# ReproAmp_V87_Stage_v0_01.net
KiCad netlist of a schematic drawn in Altium Designer
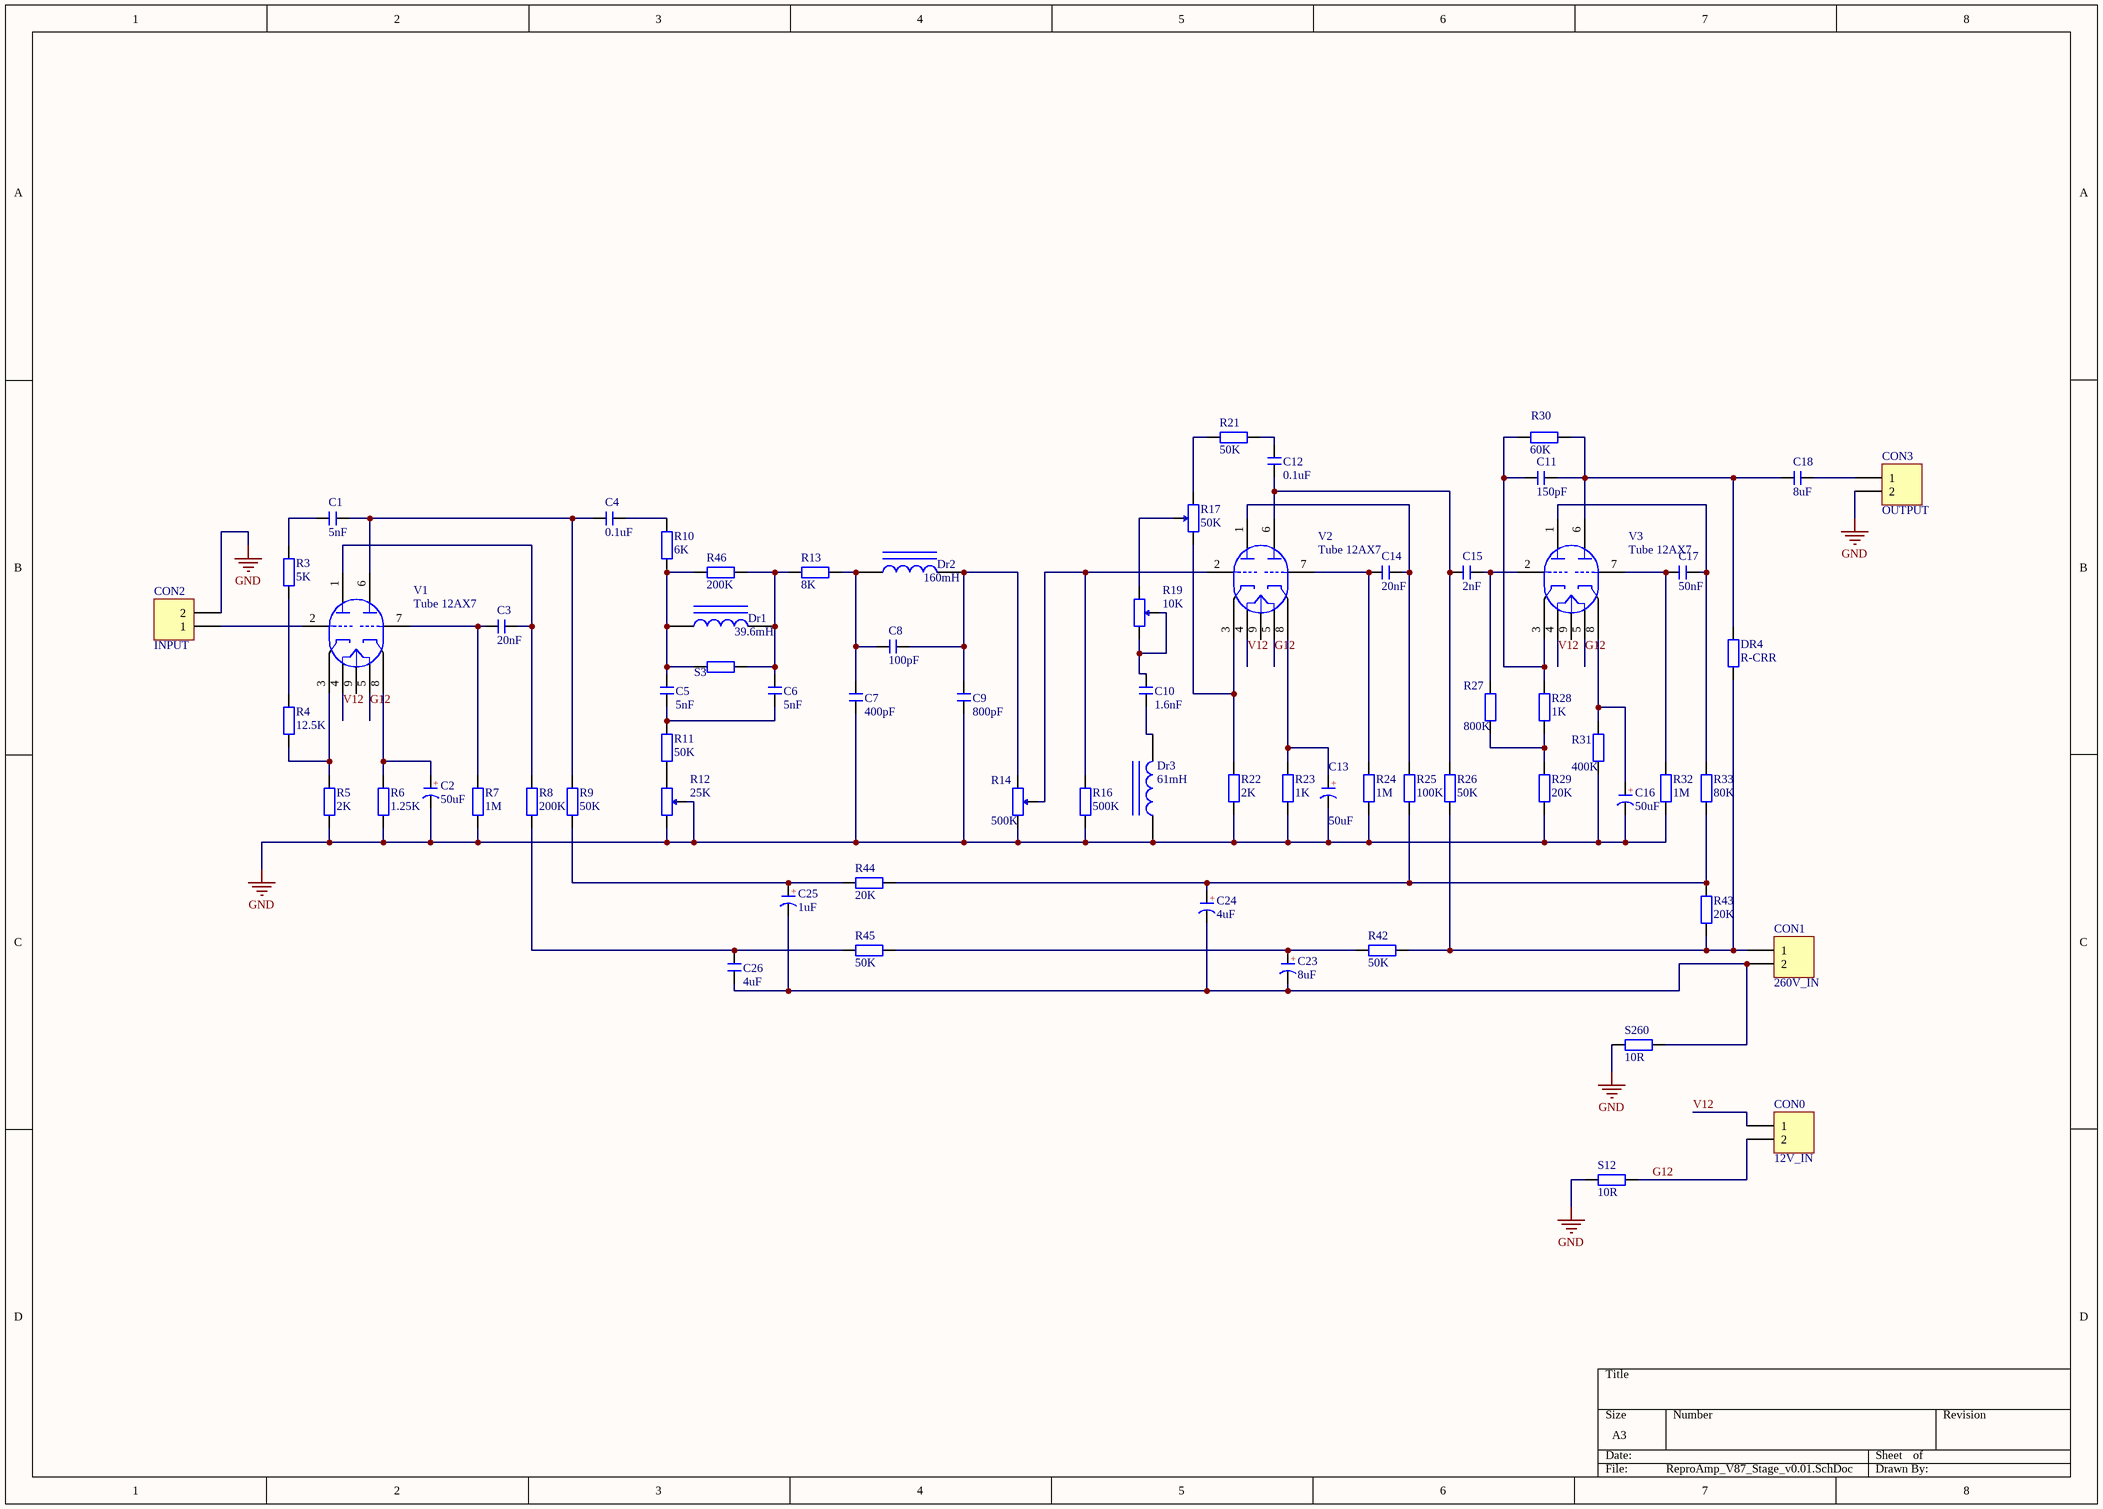
[diagram p0: ReproAmp_V87_Stage_v0.01.SchDoc]

(export (version "E")
  (design (tool "Eeschema 10.0.6"))
  (components
    (comp (ref "C1")
      (value "5nF")
      (footprint "CY 7.5*10*4")
      (description "CBB电容")
      (fields (field (name "版权归属") "源创客"))
      (libsource (lib "电阻-电容-电感") (part "C-CBB"))
    )
    (comp (ref "C2")
      (value "50uF")
      (footprint "CAP 5.0*12.5*20")
      (description "直插电解电容")
      (fields (field (name "版权归属") "源创客"))
      (libsource (lib "电阻-电容-电感") (part "C-CAP"))
    )
    (comp (ref "C3")
      (value "20nF")
      (footprint "CBB 10*12*8")
      (description "CBB电容")
      (fields (field (name "版权归属") "源创客"))
      (libsource (lib "电阻-电容-电感") (part "C-CBB"))
    )
    (comp (ref "C4")
      (value "0.1uF")
      (footprint "CBB 15*18*11")
      (description "CBB电容")
      (fields (field (name "版权归属") "源创客"))
      (libsource (lib "电阻-电容-电感") (part "C-CBB"))
    )
    (comp (ref "C5")
      (value "5nF")
      (footprint "CBB 7.2*7.2*13")
      (description "CBB电容")
      (fields (field (name "版权归属") "源创客"))
      (libsource (lib "电阻-电容-电感") (part "C-CBB"))
    )
    (comp (ref "C6")
      (value "5nF")
      (footprint "CBB 7.2*7.2*13")
      (description "CBB电容")
      (fields (field (name "版权归属") "源创客"))
      (libsource (lib "电阻-电容-电感") (part "C-CBB"))
    )
    (comp (ref "C7")
      (value "400pF")
      (footprint "CBB 7.2*7.2*13")
      (description "CBB电容")
      (fields (field (name "版权归属") "源创客"))
      (libsource (lib "电阻-电容-电感") (part "C-CBB"))
    )
    (comp (ref "C8")
      (value "100pF")
      (footprint "CBB 7.2*7.2*13")
      (description "CBB电容")
      (fields (field (name "版权归属") "源创客"))
      (libsource (lib "电阻-电容-电感") (part "C-CBB"))
    )
    (comp (ref "C9")
      (value "800pF")
      (footprint "CBB 7.2*7.2*13")
      (description "CBB电容")
      (fields (field (name "版权归属") "源创客"))
      (libsource (lib "电阻-电容-电感") (part "C-CBB"))
    )
    (comp (ref "C10")
      (value "1.6nF")
      (footprint "CBB 7.2*7.2*13")
      (description "CBB电容")
      (fields (field (name "版权归属") "源创客"))
      (libsource (lib "电阻-电容-电感") (part "C-CBB"))
    )
    (comp (ref "C11")
      (value "150pF")
      (footprint "CBB 15*18*11")
      (description "CBB电容")
      (fields (field (name "版权归属") "源创客"))
      (libsource (lib "电阻-电容-电感") (part "C-CBB"))
    )
    (comp (ref "C12")
      (value "0.1uF")
      (footprint "CBB 15*18*11")
      (description "CBB电容")
      (fields (field (name "版权归属") "源创客"))
      (libsource (lib "电阻-电容-电感") (part "C-CBB"))
    )
    (comp (ref "C13")
      (value "50uF")
      (footprint "CAP 5.0*12.5*20")
      (description "直插电解电容")
      (fields (field (name "版权归属") "源创客"))
      (libsource (lib "电阻-电容-电感") (part "C-CAP"))
    )
    (comp (ref "C14")
      (value "20nF")
      (footprint "CBB 10*12*8")
      (description "CBB电容")
      (fields (field (name "版权归属") "源创客"))
      (libsource (lib "电阻-电容-电感") (part "C-CBB"))
    )
    (comp (ref "C15")
      (value "2nF")
      (footprint "CY 7.5*8*4")
      (description "CBB电容")
      (fields (field (name "版权归属") "源创客"))
      (libsource (lib "电阻-电容-电感") (part "C-CBB"))
    )
    (comp (ref "C16")
      (value "50uF")
      (footprint "CAP 5.0*12.5*20")
      (description "直插电解电容")
      (fields (field (name "版权归属") "源创客"))
      (libsource (lib "电阻-电容-电感") (part "C-CAP"))
    )
    (comp (ref "C17")
      (value "50nF")
      (footprint "CBB 15*18*11")
      (description "CBB电容")
      (fields (field (name "版权归属") "源创客"))
      (libsource (lib "电阻-电容-电感") (part "C-CBB"))
    )
    (comp (ref "C18")
      (value "8uF")
      (footprint "CBB 50*30*30")
      (description "CBB电容")
      (fields (field (name "版权归属") "源创客"))
      (libsource (lib "电阻-电容-电感") (part "C-CBB"))
    )
    (comp (ref "C23")
      (value "8uF")
      (footprint "CAP 5.0*12.5*20")
      (description "直插电解电容")
      (fields (field (name "版权归属") "源创客"))
      (libsource (lib "电阻-电容-电感") (part "C-CAP"))
    )
    (comp (ref "C24")
      (value "4uF")
      (footprint "CAP 5.0*12.5*20")
      (description "直插电解电容")
      (fields (field (name "版权归属") "源创客"))
      (libsource (lib "电阻-电容-电感") (part "C-CAP"))
    )
    (comp (ref "C25")
      (value "1uF")
      (footprint "CAP 5.0*12.5*20")
      (description "直插电解电容")
      (fields (field (name "版权归属") "源创客"))
      (libsource (lib "电阻-电容-电感") (part "C-CAP"))
    )
    (comp (ref "C26")
      (value "4uF")
      (footprint "CBB 20*23*17")
      (description "CBB电容")
      (fields (field (name "版权归属") "源创客"))
      (libsource (lib "电阻-电容-电感") (part "C-CBB"))
    )
    (comp (ref "CON0") (value "12V_IN") (footprint "HX5.08-2L") (libsource (lib "") (part "EDG5.08-2P_1")))
    (comp (ref "CON1") (value "260V_IN") (footprint "HX5.08-2L") (libsource (lib "") (part "EDG5.08-2P_1")))
    (comp (ref "CON2")
      (value "INPUT")
      (footprint "HX5.08-2L")
      (libsource (lib "Connectors") (part "EDG5.08-2P"))
    )
    (comp (ref "CON3") (value "OUTPUT") (footprint "HX5.08-2L") (libsource (lib "") (part "EDG5.08-2P_1")))
    (comp (ref "Dr1")
      (value "39.6mH")
      (footprint "AXIAL-0.5")
      (description "Magnetic-Core Inductor")
      (fields (field (name "PUBLISHER") "Altium Limited"))
      (libsource (lib "Miscellaneous Devices") (part "Inductor Iron"))
    )
    (comp (ref "Dr2")
      (value "160mH")
      (footprint "AXIAL-0.5")
      (description "Magnetic-Core Inductor")
      (fields (field (name "PUBLISHER") "Altium Limited"))
      (libsource (lib "Miscellaneous Devices") (part "Inductor Iron"))
    )
    (comp (ref "Dr3")
      (value "61mH")
      (footprint "AXIAL-0.5")
      (description "Magnetic-Core Inductor")
      (fields (field (name "PUBLISHER") "Altium Limited"))
      (libsource (lib "Miscellaneous Devices") (part "Inductor Iron"))
    )
    (comp (ref "DR4")
      (value "R-CRR")
      (footprint "RS 2W")
      (description "直插色环电阻")
      (fields (field (name "版权归属") "源创客"))
      (libsource (lib "电阻-电容-电感") (part "R-CRR"))
    )
    (comp (ref "R3")
      (value "5K")
      (footprint "RS 1W")
      (description "直插色环电阻")
      (fields (field (name "版权归属") "源创客"))
      (libsource (lib "电阻-电容-电感") (part "R-CRR"))
    )
    (comp (ref "R4")
      (value "12.5K")
      (footprint "RS 1W")
      (description "直插色环电阻")
      (fields (field (name "版权归属") "源创客"))
      (libsource (lib "电阻-电容-电感") (part "R-CRR"))
    )
    (comp (ref "R5")
      (value "2K")
      (footprint "RS 1W")
      (description "直插色环电阻")
      (fields (field (name "版权归属") "源创客"))
      (libsource (lib "电阻-电容-电感") (part "R-CRR"))
    )
    (comp (ref "R6")
      (value "1.25K")
      (footprint "RS 1W")
      (description "直插色环电阻")
      (fields (field (name "版权归属") "源创客"))
      (libsource (lib "电阻-电容-电感") (part "R-CRR"))
    )
    (comp (ref "R7")
      (value "1M")
      (footprint "RS 1W")
      (description "直插色环电阻")
      (fields (field (name "版权归属") "源创客"))
      (libsource (lib "电阻-电容-电感") (part "R-CRR"))
    )
    (comp (ref "R8")
      (value "200K")
      (footprint "RS 1W")
      (description "直插色环电阻")
      (fields (field (name "版权归属") "源创客"))
      (libsource (lib "电阻-电容-电感") (part "R-CRR"))
    )
    (comp (ref "R9")
      (value "50K")
      (footprint "RS 2W")
      (description "直插色环电阻")
      (fields (field (name "版权归属") "源创客"))
      (libsource (lib "电阻-电容-电感") (part "R-CRR"))
    )
    (comp (ref "R10")
      (value "6K")
      (footprint "RS 1/2W")
      (description "直插色环电阻")
      (fields (field (name "版权归属") "源创客"))
      (libsource (lib "电阻-电容-电感") (part "R-CRR"))
    )
    (comp (ref "R11")
      (value "50K")
      (footprint "RS 1/2W")
      (description "直插色环电阻")
      (fields (field (name "版权归属") "源创客"))
      (libsource (lib "电阻-电容-电感") (part "R-CRR"))
    )
    (comp (ref "R12")
      (value "25K")
      (footprint "RS 1/2W-VR")
      (description "直插可调电阻-顶调")
      (libsource (lib "电阻-电容-电感") (part "VR-W"))
    )
    (comp (ref "R13")
      (value "8K")
      (footprint "RS 1/2W")
      (description "直插色环电阻")
      (fields (field (name "版权归属") "源创客"))
      (libsource (lib "电阻-电容-电感") (part "R-CRR"))
    )
    (comp (ref "R14")
      (value "500K")
      (footprint "RS 1/2W-VR")
      (description "直插可调电阻-顶调")
      (libsource (lib "电阻-电容-电感") (part "VR-W"))
    )
    (comp (ref "R16")
      (value "500K")
      (footprint "RS 1W")
      (description "直插色环电阻")
      (fields (field (name "版权归属") "源创客"))
      (libsource (lib "电阻-电容-电感") (part "R-CRR"))
    )
    (comp (ref "R17")
      (value "50K")
      (footprint "RS 1/2W-VR")
      (description "直插可调电阻-顶调")
      (libsource (lib "电阻-电容-电感") (part "VR-W"))
    )
    (comp (ref "R19")
      (value "10K")
      (footprint "RS 1/2W-VR")
      (description "直插可调电阻-顶调")
      (libsource (lib "电阻-电容-电感") (part "VR-W"))
    )
    (comp (ref "R21")
      (value "50K")
      (footprint "RS 1W")
      (description "直插色环电阻")
      (fields (field (name "版权归属") "源创客"))
      (libsource (lib "电阻-电容-电感") (part "R-CRR"))
    )
    (comp (ref "R22")
      (value "2K")
      (footprint "RS 1W")
      (description "直插色环电阻")
      (fields (field (name "版权归属") "源创客"))
      (libsource (lib "电阻-电容-电感") (part "R-CRR"))
    )
    (comp (ref "R23")
      (value "1K")
      (footprint "RS 1W")
      (description "直插色环电阻")
      (fields (field (name "版权归属") "源创客"))
      (libsource (lib "电阻-电容-电感") (part "R-CRR"))
    )
    (comp (ref "R24")
      (value "1M")
      (footprint "RS 1W")
      (description "直插色环电阻")
      (fields (field (name "版权归属") "源创客"))
      (libsource (lib "电阻-电容-电感") (part "R-CRR"))
    )
    (comp (ref "R25")
      (value "100K")
      (footprint "RS 2W")
      (description "直插色环电阻")
      (fields (field (name "版权归属") "源创客"))
      (libsource (lib "电阻-电容-电感") (part "R-CRR"))
    )
    (comp (ref "R26")
      (value "50K")
      (footprint "RS 1W")
      (description "直插色环电阻")
      (fields (field (name "版权归属") "源创客"))
      (libsource (lib "电阻-电容-电感") (part "R-CRR"))
    )
    (comp (ref "R27")
      (value "800K")
      (footprint "RS 1W")
      (description "直插色环电阻")
      (fields (field (name "版权归属") "源创客"))
      (libsource (lib "电阻-电容-电感") (part "R-CRR"))
    )
    (comp (ref "R28")
      (value "1K")
      (footprint "RS 1W")
      (description "直插色环电阻")
      (fields (field (name "版权归属") "源创客"))
      (libsource (lib "电阻-电容-电感") (part "R-CRR"))
    )
    (comp (ref "R29")
      (value "20K")
      (footprint "RS 1W")
      (description "直插色环电阻")
      (fields (field (name "版权归属") "源创客"))
      (libsource (lib "电阻-电容-电感") (part "R-CRR"))
    )
    (comp (ref "R30")
      (value "60K")
      (footprint "RS 1W")
      (description "直插色环电阻")
      (fields (field (name "版权归属") "源创客"))
      (libsource (lib "电阻-电容-电感") (part "R-CRR"))
    )
    (comp (ref "R31")
      (value "400K")
      (footprint "RS 1W")
      (description "直插色环电阻")
      (fields (field (name "版权归属") "源创客"))
      (libsource (lib "电阻-电容-电感") (part "R-CRR"))
    )
    (comp (ref "R32")
      (value "1M")
      (footprint "RS 1W")
      (description "直插色环电阻")
      (fields (field (name "版权归属") "源创客"))
      (libsource (lib "电阻-电容-电感") (part "R-CRR"))
    )
    (comp (ref "R33")
      (value "80K")
      (footprint "RS 2W")
      (description "直插色环电阻")
      (fields (field (name "版权归属") "源创客"))
      (libsource (lib "电阻-电容-电感") (part "R-CRR"))
    )
    (comp (ref "R42")
      (value "50K")
      (footprint "RS 1W")
      (description "直插色环电阻")
      (fields (field (name "版权归属") "源创客"))
      (libsource (lib "电阻-电容-电感") (part "R-CRR"))
    )
    (comp (ref "R43")
      (value "20K")
      (footprint "RS 1W")
      (description "直插色环电阻")
      (fields (field (name "版权归属") "源创客"))
      (libsource (lib "电阻-电容-电感") (part "R-CRR"))
    )
    (comp (ref "R44")
      (value "20K")
      (footprint "RS 1W")
      (description "直插色环电阻")
      (fields (field (name "版权归属") "源创客"))
      (libsource (lib "电阻-电容-电感") (part "R-CRR"))
    )
    (comp (ref "R45")
      (value "50K")
      (footprint "RS 1W")
      (description "直插色环电阻")
      (fields (field (name "版权归属") "源创客"))
      (libsource (lib "电阻-电容-电感") (part "R-CRR"))
    )
    (comp (ref "R46")
      (value "200K")
      (footprint "RS 1/2W")
      (description "直插色环电阻")
      (fields (field (name "版权归属") "源创客"))
      (libsource (lib "电阻-电容-电感") (part "R-CRR"))
    )
    (comp (ref "S3")
      (value "0")
      (footprint "RS 1/2W")
      (description "直插色环电阻")
      (fields (field (name "版权归属") "源创客"))
      (libsource (lib "电阻-电容-电感") (part "R-CRR"))
    )
    (comp (ref "S12")
      (value "10R")
      (footprint "RS 1W")
      (description "直插色环电阻")
      (fields (field (name "版权归属") "源创客"))
      (libsource (lib "电阻-电容-电感") (part "R-CRR"))
    )
    (comp (ref "S260")
      (value "10R")
      (footprint "RS 1W")
      (description "直插色环电阻")
      (fields (field (name "版权归属") "源创客"))
      (libsource (lib "电阻-电容-电感") (part "R-CRR"))
    )
    (comp (ref "V1")
      (value "Tube 12AX7")
      (footprint "VTUBE-9-W")
      (description "High Mu Dual Triode")
      (fields (field (name "PUBLISHER") "Altium Limited"))
      (libsource (lib "Miscellaneous Devices") (part "Tube 12AX7"))
    )
    (comp (ref "V2")
      (value "Tube 12AX7")
      (footprint "VTUBE-9-W")
      (description "High Mu Dual Triode")
      (fields (field (name "PUBLISHER") "Altium Limited"))
      (libsource (lib "Miscellaneous Devices") (part "Tube 12AX7"))
    )
    (comp (ref "V3")
      (value "Tube 12AX7")
      (footprint "VTUBE-9-W")
      (description "High Mu Dual Triode")
      (fields (field (name "PUBLISHER") "Altium Limited"))
      (libsource (lib "Miscellaneous Devices") (part "Tube 12AX7"))
    )
  )
  (nets
    (net (code "1") (name "/G12") (class "Default")
      (node (ref "CON0") (pin "2") (pinfunction "2_2") (pintype "passive"))
      (node (ref "S12") (pin "2") (pinfunction "2_2") (pintype "passive"))
      (node (ref "V1") (pin "5") (pinfunction "H_5") (pintype "passive"))
      (node (ref "V2") (pin "5") (pinfunction "H_5") (pintype "passive"))
      (node (ref "V3") (pin "5") (pinfunction "H_5") (pintype "passive"))
    )
    (net (code "2") (name "/V12") (class "Default")
      (node (ref "CON0") (pin "1") (pinfunction "1_1") (pintype "passive"))
      (node (ref "V1") (pin "4") (pinfunction "H_4") (pintype "passive"))
      (node (ref "V2") (pin "4") (pinfunction "H_4") (pintype "passive"))
      (node (ref "V3") (pin "4") (pinfunction "H_4") (pintype "passive"))
    )
    (net (code "3") (name "GND") (class "Default")
      (node (ref "C13") (pin "2") (pinfunction "K_2") (pintype "passive"))
      (node (ref "C16") (pin "2") (pinfunction "K_2") (pintype "passive"))
      (node (ref "C2") (pin "2") (pinfunction "K_2") (pintype "passive"))
      (node (ref "C7") (pin "1") (pinfunction "1_1") (pintype "passive"))
      (node (ref "C9") (pin "1") (pinfunction "1_1") (pintype "passive"))
      (node (ref "CON2") (pin "2") (pinfunction "2_2") (pintype "passive"))
      (node (ref "CON3") (pin "2") (pinfunction "2_2") (pintype "passive"))
      (node (ref "Dr3") (pin "1") (pinfunction "1_1") (pintype "passive"))
      (node (ref "R12") (pin "2") (pinfunction "2_2") (pintype "passive"))
      (node (ref "R12") (pin "3") (pinfunction "3_3") (pintype "passive"))
      (node (ref "R14") (pin "2") (pinfunction "2_2") (pintype "passive"))
      (node (ref "R16") (pin "1") (pinfunction "1_1") (pintype "passive"))
      (node (ref "R22") (pin "1") (pinfunction "1_1") (pintype "passive"))
      (node (ref "R23") (pin "1") (pinfunction "1_1") (pintype "passive"))
      (node (ref "R24") (pin "1") (pinfunction "1_1") (pintype "passive"))
      (node (ref "R29") (pin "1") (pinfunction "1_1") (pintype "passive"))
      (node (ref "R31") (pin "2") (pinfunction "2_2") (pintype "passive"))
      (node (ref "R32") (pin "2") (pinfunction "2_2") (pintype "passive"))
      (node (ref "R5") (pin "1") (pinfunction "1_1") (pintype "passive"))
      (node (ref "R6") (pin "1") (pinfunction "1_1") (pintype "passive"))
      (node (ref "R7") (pin "1") (pinfunction "1_1") (pintype "passive"))
      (node (ref "S12") (pin "1") (pinfunction "1_1") (pintype "passive"))
      (node (ref "S260") (pin "1") (pinfunction "1_1") (pintype "passive"))
    )
    (net (code "4") (name "Net-(C1-Pad1)") (class "Default")
      (node (ref "C1") (pin "1") (pinfunction "1_1") (pintype "passive"))
      (node (ref "R3") (pin "2") (pinfunction "2_2") (pintype "passive"))
    )
    (net (code "5") (name "Net-(C2-A)") (class "Default")
      (node (ref "C2") (pin "1") (pinfunction "A_1") (pintype "passive"))
      (node (ref "R6") (pin "2") (pinfunction "2_2") (pintype "passive"))
      (node (ref "V1") (pin "8") (pinfunction "KT2_8") (pintype "passive"))
    )
    (net (code "6") (name "Net-(C4-Pad2)") (class "Default")
      (node (ref "C4") (pin "2") (pinfunction "2_2") (pintype "passive"))
      (node (ref "R10") (pin "2") (pinfunction "2_2") (pintype "passive"))
    )
    (net (code "7") (name "Net-(C5-Pad1)") (class "Default")
      (node (ref "C5") (pin "1") (pinfunction "1_1") (pintype "passive"))
      (node (ref "C6") (pin "1") (pinfunction "1_1") (pintype "passive"))
      (node (ref "R11") (pin "2") (pinfunction "2_2") (pintype "passive"))
    )
    (net (code "8") (name "Net-(C5-Pad2)") (class "Default")
      (node (ref "C5") (pin "2") (pinfunction "2_2") (pintype "passive"))
      (node (ref "Dr1") (pin "1") (pinfunction "1_1") (pintype "passive"))
      (node (ref "R10") (pin "1") (pinfunction "1_1") (pintype "passive"))
      (node (ref "R46") (pin "1") (pinfunction "1_1") (pintype "passive"))
      (node (ref "S3") (pin "1") (pinfunction "1_1") (pintype "passive"))
    )
    (net (code "9") (name "Net-(C6-Pad2)") (class "Default")
      (node (ref "C6") (pin "2") (pinfunction "2_2") (pintype "passive"))
      (node (ref "Dr1") (pin "2") (pinfunction "2_2") (pintype "passive"))
      (node (ref "R13") (pin "1") (pinfunction "1_1") (pintype "passive"))
      (node (ref "R46") (pin "2") (pinfunction "2_2") (pintype "passive"))
      (node (ref "S3") (pin "2") (pinfunction "2_2") (pintype "passive"))
    )
    (net (code "10") (name "Net-(C7-Pad2)") (class "Default")
      (node (ref "C7") (pin "2") (pinfunction "2_2") (pintype "passive"))
      (node (ref "C8") (pin "2") (pinfunction "2_2") (pintype "passive"))
      (node (ref "Dr2") (pin "1") (pinfunction "1_1") (pintype "passive"))
      (node (ref "R13") (pin "2") (pinfunction "2_2") (pintype "passive"))
    )
    (net (code "11") (name "Net-(C8-Pad1)") (class "Default")
      (node (ref "C8") (pin "1") (pinfunction "1_1") (pintype "passive"))
      (node (ref "C9") (pin "2") (pinfunction "2_2") (pintype "passive"))
      (node (ref "Dr2") (pin "2") (pinfunction "2_2") (pintype "passive"))
      (node (ref "R14") (pin "1") (pinfunction "1_1") (pintype "passive"))
    )
    (net (code "12") (name "Net-(C10-Pad1)") (class "Default")
      (node (ref "C10") (pin "1") (pinfunction "1_1") (pintype "passive"))
      (node (ref "Dr3") (pin "2") (pinfunction "2_2") (pintype "passive"))
    )
    (net (code "13") (name "Net-(C10-Pad2)") (class "Default")
      (node (ref "C10") (pin "2") (pinfunction "2_2") (pintype "passive"))
      (node (ref "R19") (pin "2") (pinfunction "2_2") (pintype "passive"))
      (node (ref "R19") (pin "3") (pinfunction "3_3") (pintype "passive"))
    )
    (net (code "14") (name "Net-(C12-Pad2)") (class "Default")
      (node (ref "C12") (pin "2") (pinfunction "2_2") (pintype "passive"))
      (node (ref "R21") (pin "2") (pinfunction "2_2") (pintype "passive"))
    )
    (net (code "15") (name "Net-(C13-A)") (class "Default")
      (node (ref "C13") (pin "1") (pinfunction "A_1") (pintype "passive"))
      (node (ref "R23") (pin "2") (pinfunction "2_2") (pintype "passive"))
      (node (ref "V2") (pin "8") (pinfunction "KT2_8") (pintype "passive"))
    )
    (net (code "16") (name "Net-(C16-A)") (class "Default")
      (node (ref "C16") (pin "1") (pinfunction "A_1") (pintype "passive"))
      (node (ref "R31") (pin "1") (pinfunction "1_1") (pintype "passive"))
      (node (ref "V3") (pin "8") (pinfunction "KT2_8") (pintype "passive"))
    )
    (net (code "17") (name "Net-(C18-Pad2)") (class "Default")
      (node (ref "C18") (pin "2") (pinfunction "2_2") (pintype "passive"))
      (node (ref "CON3") (pin "1") (pinfunction "1_1") (pintype "passive"))
    )
    (net (code "18") (name "Net-(C23-A)") (class "Default")
      (node (ref "C23") (pin "1") (pinfunction "A_1") (pintype "passive"))
      (node (ref "R42") (pin "1") (pinfunction "1_1") (pintype "passive"))
      (node (ref "R45") (pin "2") (pinfunction "2_2") (pintype "passive"))
    )
    (net (code "19") (name "Net-(C23-K)") (class "Default")
      (node (ref "C23") (pin "2") (pinfunction "K_2") (pintype "passive"))
      (node (ref "C24") (pin "2") (pinfunction "K_2") (pintype "passive"))
      (node (ref "C25") (pin "2") (pinfunction "K_2") (pintype "passive"))
      (node (ref "C26") (pin "2") (pinfunction "2_2") (pintype "passive"))
      (node (ref "CON1") (pin "2") (pinfunction "2_2") (pintype "passive"))
      (node (ref "S260") (pin "2") (pinfunction "2_2") (pintype "passive"))
    )
    (net (code "20") (name "Net-(C24-A)") (class "Default")
      (node (ref "C24") (pin "1") (pinfunction "A_1") (pintype "passive"))
      (node (ref "R25") (pin "1") (pinfunction "1_1") (pintype "passive"))
      (node (ref "R33") (pin "2") (pinfunction "2_2") (pintype "passive"))
      (node (ref "R43") (pin "2") (pinfunction "2_2") (pintype "passive"))
      (node (ref "R44") (pin "2") (pinfunction "2_2") (pintype "passive"))
    )
    (net (code "21") (name "Net-(C25-A)") (class "Default")
      (node (ref "C25") (pin "1") (pinfunction "A_1") (pintype "passive"))
      (node (ref "R44") (pin "1") (pinfunction "1_1") (pintype "passive"))
      (node (ref "R9") (pin "1") (pinfunction "1_1") (pintype "passive"))
    )
    (net (code "22") (name "Net-(C26-Pad1)") (class "Default")
      (node (ref "C26") (pin "1") (pinfunction "1_1") (pintype "passive"))
      (node (ref "R45") (pin "1") (pinfunction "1_1") (pintype "passive"))
      (node (ref "R8") (pin "1") (pinfunction "1_1") (pintype "passive"))
    )
    (net (code "23") (name "Net-(CON1-Pad1)") (class "Default")
      (node (ref "CON1") (pin "1") (pinfunction "1_1") (pintype "passive"))
      (node (ref "DR4") (pin "1") (pinfunction "1_1") (pintype "passive"))
      (node (ref "R26") (pin "1") (pinfunction "1_1") (pintype "passive"))
      (node (ref "R42") (pin "2") (pinfunction "2_2") (pintype "passive"))
      (node (ref "R43") (pin "1") (pinfunction "1_1") (pintype "passive"))
    )
    (net (code "24") (name "Net-(R3-Pad1)") (class "Default")
      (node (ref "R3") (pin "1") (pinfunction "1_1") (pintype "passive"))
      (node (ref "R4") (pin "2") (pinfunction "2_2") (pintype "passive"))
    )
    (net (code "25") (name "Net-(R11-Pad1)") (class "Default")
      (node (ref "R11") (pin "1") (pinfunction "1_1") (pintype "passive"))
      (node (ref "R12") (pin "1") (pinfunction "1_1") (pintype "passive"))
    )
    (net (code "26") (name "Net-(R17-Pad1)") (class "Default")
      (node (ref "R17") (pin "1") (pinfunction "1_1") (pintype "passive"))
      (node (ref "R21") (pin "1") (pinfunction "1_1") (pintype "passive"))
    )
    (net (code "27") (name "Net-(R17-Pad3)") (class "Default")
      (node (ref "R17") (pin "3") (pinfunction "3_3") (pintype "passive"))
      (node (ref "R19") (pin "1") (pinfunction "1_1") (pintype "passive"))
    )
    (net (code "28") (name "Net-(R27-Pad1)") (class "Default")
      (node (ref "R27") (pin "1") (pinfunction "1_1") (pintype "passive"))
      (node (ref "R28") (pin "1") (pinfunction "1_1") (pintype "passive"))
      (node (ref "R29") (pin "2") (pinfunction "2_2") (pintype "passive"))
    )
    (net (code "29") (name "Net-(V1-GT1)") (class "Default")
      (node (ref "CON2") (pin "1") (pinfunction "1_1") (pintype "passive"))
      (node (ref "V1") (pin "2") (pinfunction "GT1_2") (pintype "passive"))
    )
    (net (code "30") (name "Net-(V1-GT2)") (class "Default")
      (node (ref "C3") (pin "1") (pinfunction "1_1") (pintype "passive"))
      (node (ref "R7") (pin "2") (pinfunction "2_2") (pintype "passive"))
      (node (ref "V1") (pin "7") (pinfunction "GT2_7") (pintype "passive"))
    )
    (net (code "31") (name "Net-(V1-KT1)") (class "Default")
      (node (ref "R4") (pin "1") (pinfunction "1_1") (pintype "passive"))
      (node (ref "R5") (pin "2") (pinfunction "2_2") (pintype "passive"))
      (node (ref "V1") (pin "3") (pinfunction "KT1_3") (pintype "passive"))
    )
    (net (code "32") (name "Net-(V1-PT1)") (class "Default")
      (node (ref "C3") (pin "2") (pinfunction "2_2") (pintype "passive"))
      (node (ref "R8") (pin "2") (pinfunction "2_2") (pintype "passive"))
      (node (ref "V1") (pin "1") (pinfunction "PT1_1") (pintype "passive"))
    )
    (net (code "33") (name "Net-(V1-PT2)") (class "Default")
      (node (ref "C1") (pin "2") (pinfunction "2_2") (pintype "passive"))
      (node (ref "C4") (pin "1") (pinfunction "1_1") (pintype "passive"))
      (node (ref "R9") (pin "2") (pinfunction "2_2") (pintype "passive"))
      (node (ref "V1") (pin "6") (pinfunction "PT2_6") (pintype "passive"))
    )
    (net (code "34") (name "Net-(V2-GT1)") (class "Default")
      (node (ref "R14") (pin "3") (pinfunction "3_3") (pintype "passive"))
      (node (ref "R16") (pin "2") (pinfunction "2_2") (pintype "passive"))
      (node (ref "V2") (pin "2") (pinfunction "GT1_2") (pintype "passive"))
    )
    (net (code "35") (name "Net-(V2-GT2)") (class "Default")
      (node (ref "C14") (pin "1") (pinfunction "1_1") (pintype "passive"))
      (node (ref "R24") (pin "2") (pinfunction "2_2") (pintype "passive"))
      (node (ref "V2") (pin "7") (pinfunction "GT2_7") (pintype "passive"))
    )
    (net (code "36") (name "Net-(V2-KT1)") (class "Default")
      (node (ref "R17") (pin "2") (pinfunction "2_2") (pintype "passive"))
      (node (ref "R22") (pin "2") (pinfunction "2_2") (pintype "passive"))
      (node (ref "V2") (pin "3") (pinfunction "KT1_3") (pintype "passive"))
    )
    (net (code "37") (name "Net-(V2-PT1)") (class "Default")
      (node (ref "C14") (pin "2") (pinfunction "2_2") (pintype "passive"))
      (node (ref "R25") (pin "2") (pinfunction "2_2") (pintype "passive"))
      (node (ref "V2") (pin "1") (pinfunction "PT1_1") (pintype "passive"))
    )
    (net (code "38") (name "Net-(V2-PT2)") (class "Default")
      (node (ref "C12") (pin "1") (pinfunction "1_1") (pintype "passive"))
      (node (ref "C15") (pin "1") (pinfunction "1_1") (pintype "passive"))
      (node (ref "R26") (pin "2") (pinfunction "2_2") (pintype "passive"))
      (node (ref "V2") (pin "6") (pinfunction "PT2_6") (pintype "passive"))
    )
    (net (code "39") (name "Net-(V3-GT1)") (class "Default")
      (node (ref "C15") (pin "2") (pinfunction "2_2") (pintype "passive"))
      (node (ref "R27") (pin "2") (pinfunction "2_2") (pintype "passive"))
      (node (ref "V3") (pin "2") (pinfunction "GT1_2") (pintype "passive"))
    )
    (net (code "40") (name "Net-(V3-GT2)") (class "Default")
      (node (ref "C17") (pin "1") (pinfunction "1_1") (pintype "passive"))
      (node (ref "R32") (pin "1") (pinfunction "1_1") (pintype "passive"))
      (node (ref "V3") (pin "7") (pinfunction "GT2_7") (pintype "passive"))
    )
    (net (code "41") (name "Net-(V3-KT1)") (class "Default")
      (node (ref "C11") (pin "1") (pinfunction "1_1") (pintype "passive"))
      (node (ref "R28") (pin "2") (pinfunction "2_2") (pintype "passive"))
      (node (ref "R30") (pin "2") (pinfunction "2_2") (pintype "passive"))
      (node (ref "V3") (pin "3") (pinfunction "KT1_3") (pintype "passive"))
    )
    (net (code "42") (name "Net-(V3-PT1)") (class "Default")
      (node (ref "C17") (pin "2") (pinfunction "2_2") (pintype "passive"))
      (node (ref "R33") (pin "1") (pinfunction "1_1") (pintype "passive"))
      (node (ref "V3") (pin "1") (pinfunction "PT1_1") (pintype "passive"))
    )
    (net (code "43") (name "Net-(V3-PT2)") (class "Default")
      (node (ref "C11") (pin "2") (pinfunction "2_2") (pintype "passive"))
      (node (ref "C18") (pin "1") (pinfunction "1_1") (pintype "passive"))
      (node (ref "DR4") (pin "2") (pinfunction "2_2") (pintype "passive"))
      (node (ref "R30") (pin "1") (pinfunction "1_1") (pintype "passive"))
      (node (ref "V3") (pin "6") (pinfunction "PT2_6") (pintype "passive"))
    )
    (net (code "44") (name "unconnected-(V1-HM-Pad9)") (class "Default")
      (node (ref "V1") (pin "9") (pinfunction "HM_9") (pintype "passive"))
    )
    (net (code "45") (name "unconnected-(V2-HM-Pad9)") (class "Default")
      (node (ref "V2") (pin "9") (pinfunction "HM_9") (pintype "passive"))
    )
    (net (code "46") (name "unconnected-(V3-HM-Pad9)") (class "Default")
      (node (ref "V3") (pin "9") (pinfunction "HM_9") (pintype "passive"))
    )
  )
)
